# Transmitter.net
KiCad netlist of a schematic drawn in Altium Designer
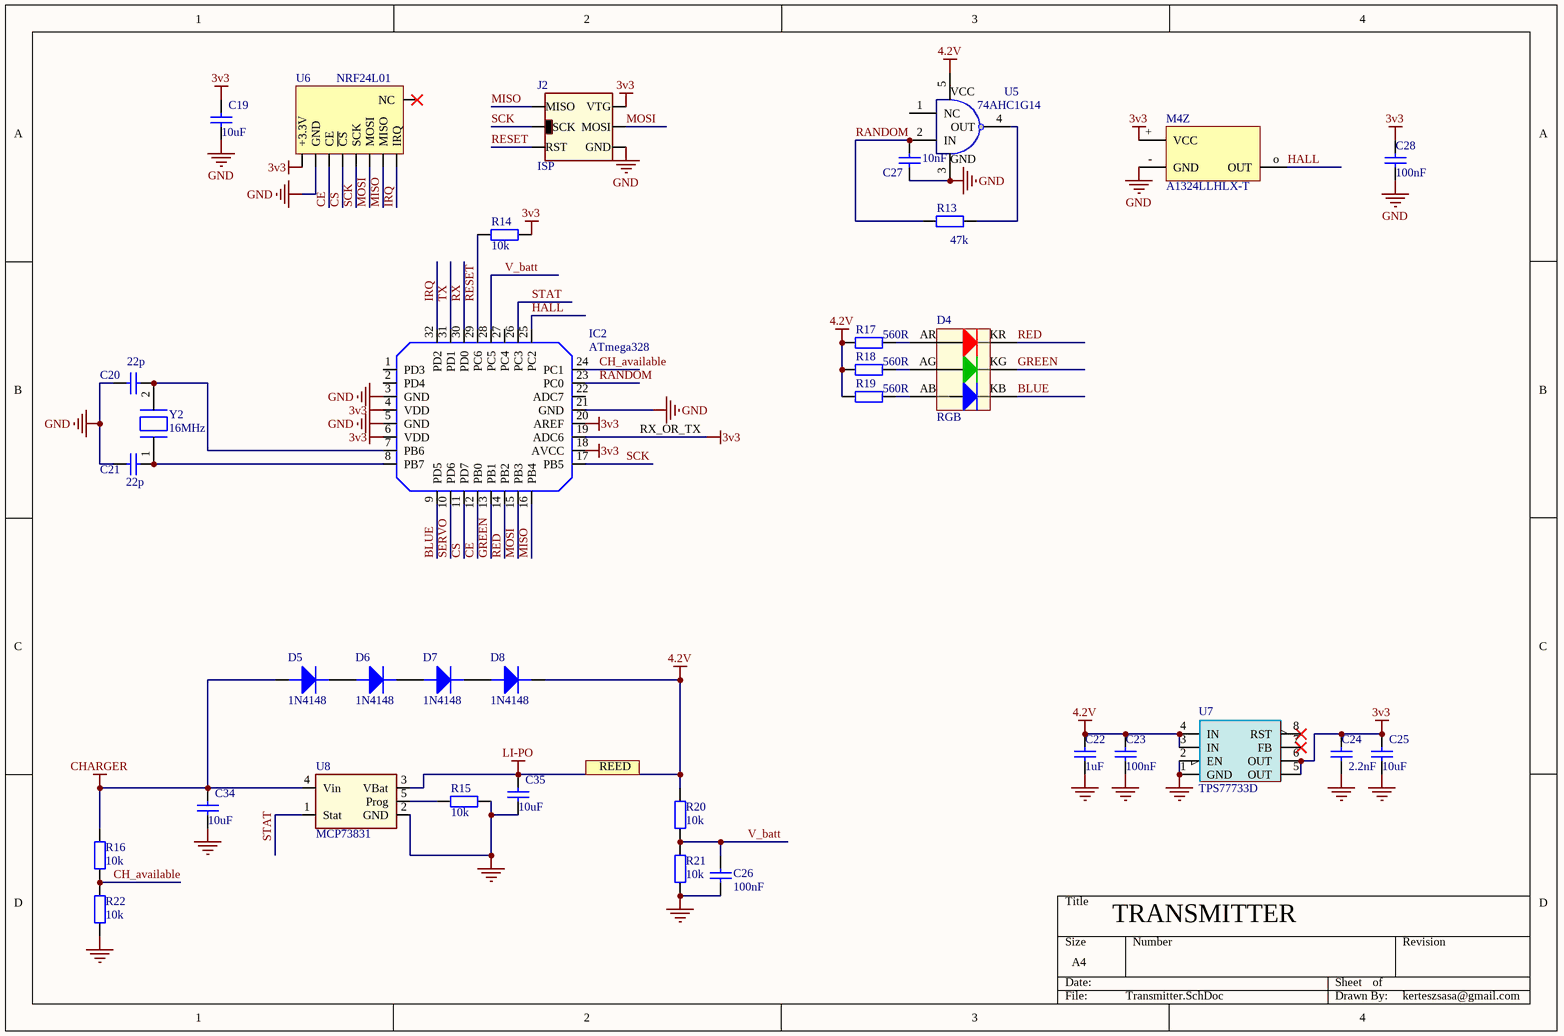
[diagram p0: Transmitter.SchDoc]

(export (version "E")
  (design (tool "Eeschema 10.0.6"))
  (components
    (comp (ref "C19")
      (value "10uF")
      (footprint "FP_0603_CAP_080")
      (description "Capacitor")
      (libsource (lib "Miscellaneous Devices") (part "Cap"))
    )
    (comp (ref "C20")
      (value "22p")
      (footprint "FP_0603_CAP_080")
      (description "Capacitor")
      (libsource (lib "Miscellaneous Devices") (part "Cap"))
    )
    (comp (ref "C21")
      (value "22p")
      (footprint "FP_0603_CAP_080")
      (description "Capacitor")
      (libsource (lib "Miscellaneous Devices") (part "Cap"))
    )
    (comp (ref "C22")
      (value "1uF")
      (footprint "FP_0603_CAP_080")
      (description "Capacitor")
      (libsource (lib "Miscellaneous Devices") (part "Cap"))
    )
    (comp (ref "C23")
      (value "100nF")
      (footprint "FP_0603_CAP_080")
      (description "Capacitor")
      (libsource (lib "Miscellaneous Devices") (part "Cap"))
    )
    (comp (ref "C24")
      (value "2.2nF")
      (footprint "FP_0603_CAP_080")
      (description "Capacitor")
      (libsource (lib "Miscellaneous Devices") (part "Cap"))
    )
    (comp (ref "C25")
      (value "10uF")
      (footprint "FP_0603_CAP_080")
      (description "Capacitor")
      (libsource (lib "Miscellaneous Devices") (part "Cap"))
    )
    (comp (ref "C26")
      (value "100nF")
      (footprint "FP_0603_CAP_080")
      (description "Capacitor")
      (libsource (lib "Miscellaneous Devices") (part "Cap"))
    )
    (comp (ref "C27")
      (value "10nF")
      (footprint "FP_0603_CAP_080")
      (description "Capacitor")
      (libsource (lib "Miscellaneous Devices") (part "Cap"))
    )
    (comp (ref "C28")
      (value "100nF")
      (footprint "FP_0603_CAP_080")
      (description "Capacitor")
      (libsource (lib "Miscellaneous Devices") (part "Cap"))
    )
    (comp (ref "C34")
      (value "10uF")
      (footprint "FP_0603_CAP_080")
      (description "Capacitor")
      (libsource (lib "Miscellaneous Devices") (part "Cap"))
    )
    (comp (ref "C35")
      (value "10uF")
      (footprint "FP_0603_CAP_080")
      (description "Capacitor")
      (libsource (lib "Miscellaneous Devices") (part "Cap"))
    )
    (comp (ref "D4")
      (value "RGB")
      (footprint "RGB_LED_5.0x5.0mm")
      (description "LED_RGB_6_PIN")
      (libsource (lib "Led_optical") (part "LED_RGB_6_PIN"))
    )
    (comp (ref "D5")
      (value "1N4148")
      (footprint "SOD-80")
      (description "Diode 1N4148 SMD")
      (libsource (lib "Diode") (part "DIODE_big"))
    )
    (comp (ref "D6")
      (value "1N4148")
      (footprint "SOD-80")
      (description "Diode 1N4148 SMD")
      (libsource (lib "Diode") (part "DIODE_big"))
    )
    (comp (ref "D7")
      (value "1N4148")
      (footprint "SOD-80")
      (description "Diode 1N4148 SMD")
      (libsource (lib "Diode") (part "DIODE_big"))
    )
    (comp (ref "D8")
      (value "1N4148")
      (footprint "SOD-80")
      (description "Diode 1N4148 SMD")
      (libsource (lib "Diode") (part "DIODE_big"))
    )
    (comp (ref "IC2") (value "ATmega328") (footprint "TQFP32_N") (libsource (lib "uC") (part "ATmega328")))
    (comp (ref "J2")
      (value "ISP")
      (footprint "AVR_ISP")
      (description "Programozó csatlakozó")
      (libsource (lib "Connector") (part "ISP"))
    )
    (comp (ref "M4Z")
      (value "A1324LLHLX-T")
      (footprint "Sensoe_hall_SOT23")
      (description "Hall-Effect Switch for High-Temperature Operation")
      (libsource (lib "Sensor") (part "A3122EUA"))
    )
    (comp (ref "R13")
      (value "47k")
      (footprint "FP_0603_RES")
      (description "Resistor")
      (libsource (lib "") (part "Res3_1"))
    )
    (comp (ref "R14")
      (value "10k")
      (footprint "FP_0603_RES")
      (description "Resistor")
      (libsource (lib "") (part "Res3_2"))
    )
    (comp (ref "R15")
      (value "10k")
      (footprint "FP_0603_RES")
      (description "Resistor")
      (libsource (lib "") (part "Res3_1"))
    )
    (comp (ref "R16")
      (value "10k")
      (footprint "FP_0603_RES")
      (description "Resistor")
      (libsource (lib "Miscellaneous Devices") (part "Res3"))
    )
    (comp (ref "R17")
      (value "560R")
      (footprint "FP_0603_RES")
      (description "Resistor")
      (libsource (lib "") (part "Res3_1"))
    )
    (comp (ref "R18")
      (value "560R")
      (footprint "FP_0603_RES")
      (description "Resistor")
      (libsource (lib "") (part "Res3_1"))
    )
    (comp (ref "R19")
      (value "560R")
      (footprint "FP_0603_RES")
      (description "Resistor")
      (libsource (lib "") (part "Res3_1"))
    )
    (comp (ref "R20")
      (value "10k")
      (footprint "FP_0603_RES")
      (description "Resistor")
      (libsource (lib "Miscellaneous Devices") (part "Res3"))
    )
    (comp (ref "R21")
      (value "10k")
      (footprint "FP_0603_RES")
      (description "Resistor")
      (libsource (lib "Miscellaneous Devices") (part "Res3"))
    )
    (comp (ref "R22")
      (value "10k")
      (footprint "FP_0603_RES")
      (description "Resistor")
      (libsource (lib "Miscellaneous Devices") (part "Res3"))
    )
    (comp (ref "U5")
      (value "74AHC1G14")
      (footprint "GATE_SOT23-5")
      (description "SCHMITT-TRIGGER INVERTER")
      (libsource (lib "Logic_gate") (part "74AHC1G14"))
    )
    (comp (ref "U6")
      (value "NRF24L01")
      (footprint "NRF24L01_SMD")
      (description "2.4Ghz RF module")
      (libsource (lib "Modul") (part "NRF24L01"))
    )
    (comp (ref "U7")
      (value "TPS77733D")
      (footprint "DIGITAL_SOIC8")
      (description "LDO Voltage Regulators Fast-Tran-Res 750-mA")
      (libsource (lib "TPS77733D") (part "TPS77733D"))
    )
    (comp (ref "U8")
      (value "MCP73831")
      (footprint "SUPPLY_SOT23-5")
      (description "MCP73831 SOT23-5 Li-on batt charger")
      (libsource (lib "Supply") (part "MCP73831"))
    )
    (comp (ref "Y2")
      (value "16MHz")
      (footprint "FP_CRYSTAL_HC49_SMD")
      (description "Standard HC49 quartz")
      (libsource (lib "Fufi_altium_lib") (part "XTAL HC49"))
    )
  )
  (nets
    (net (code "1") (name "/BLUE") (class "Default")
      (node (ref "D4") (pin "KB") (pinfunction "R_KB") (pintype "passive"))
      (node (ref "IC2") (pin "9") (pinfunction "PD5_9") (pintype "passive"))
    )
    (net (code "2") (name "/CE") (class "Default")
      (node (ref "IC2") (pin "12") (pinfunction "PB0_12") (pintype "passive"))
      (node (ref "U6") (pin "3") (pinfunction "CE_3") (pintype "passive"))
    )
    (net (code "3") (name "/CH_available") (class "Default")
      (node (ref "IC2") (pin "24") (pinfunction "PC1_24") (pintype "passive"))
      (node (ref "R16") (pin "1") (pinfunction "1_1") (pintype "passive"))
      (node (ref "R22") (pin "2") (pinfunction "2_2") (pintype "passive"))
    )
    (net (code "4") (name "/CS") (class "Default")
      (node (ref "IC2") (pin "11") (pinfunction "PD7_11") (pintype "passive"))
      (node (ref "U6") (pin "4") (pinfunction "~{CS}_4") (pintype "passive"))
    )
    (net (code "5") (name "/GREEN") (class "Default")
      (node (ref "D4") (pin "KG") (pinfunction "G_KG") (pintype "passive"))
      (node (ref "IC2") (pin "13") (pinfunction "PB1_13") (pintype "passive"))
    )
    (net (code "6") (name "/HALL") (class "Default")
      (node (ref "IC2") (pin "25") (pinfunction "PC2_25") (pintype "passive"))
      (node (ref "M4Z") (pin "o") (pinfunction "OUT_o") (pintype "open_collector"))
    )
    (net (code "7") (name "/IRQ") (class "Default")
      (node (ref "IC2") (pin "32") (pinfunction "PD2_32") (pintype "passive"))
      (node (ref "U6") (pin "8") (pinfunction "IRQ_8") (pintype "passive"))
    )
    (net (code "8") (name "/MISO") (class "Default")
      (node (ref "IC2") (pin "16") (pinfunction "PB4_16") (pintype "passive"))
      (node (ref "J2") (pin "1") (pinfunction "MISO_1") (pintype "passive"))
      (node (ref "U6") (pin "7") (pinfunction "MISO_7") (pintype "passive"))
    )
    (net (code "9") (name "/MOSI") (class "Default")
      (node (ref "IC2") (pin "15") (pinfunction "PB3_15") (pintype "passive"))
      (node (ref "J2") (pin "4") (pinfunction "MOSI_4") (pintype "passive"))
      (node (ref "U6") (pin "6") (pinfunction "MOSI_6") (pintype "passive"))
    )
    (net (code "10") (name "/RANDOM") (class "Default")
      (node (ref "C27") (pin "2") (pinfunction "2_2") (pintype "passive"))
      (node (ref "IC2") (pin "23") (pinfunction "PC0_23") (pintype "passive"))
      (node (ref "R13") (pin "2") (pinfunction "2_2") (pintype "passive"))
      (node (ref "U5") (pin "2") (pinfunction "IN_2") (pintype "passive"))
    )
    (net (code "11") (name "/RED") (class "Default")
      (node (ref "D4") (pin "KR") (pinfunction "B_KR") (pintype "passive"))
      (node (ref "IC2") (pin "14") (pinfunction "PB2_14") (pintype "passive"))
    )
    (net (code "12") (name "/RESET") (class "Default")
      (node (ref "IC2") (pin "29") (pinfunction "PC6_29") (pintype "passive"))
      (node (ref "J2") (pin "5") (pinfunction "RST_5") (pintype "passive"))
      (node (ref "R14") (pin "1") (pinfunction "1_1") (pintype "passive"))
    )
    (net (code "13") (name "/RX") (class "Default")
      (node (ref "IC2") (pin "30") (pinfunction "PD0_30") (pintype "passive"))
    )
    (net (code "14") (name "/SCK") (class "Default")
      (node (ref "IC2") (pin "17") (pinfunction "PB5_17") (pintype "passive"))
      (node (ref "J2") (pin "3") (pinfunction "SCK_3") (pintype "passive"))
      (node (ref "U6") (pin "5") (pinfunction "SCK_5") (pintype "passive"))
    )
    (net (code "15") (name "/SERVO") (class "Default")
      (node (ref "IC2") (pin "10") (pinfunction "PD6_10") (pintype "passive"))
    )
    (net (code "16") (name "/STAT") (class "Default")
      (node (ref "IC2") (pin "26") (pinfunction "PC3_26") (pintype "passive"))
      (node (ref "U8") (pin "1") (pinfunction "Stat_1") (pintype "passive"))
    )
    (net (code "17") (name "/TX") (class "Default")
      (node (ref "IC2") (pin "31") (pinfunction "PD1_31") (pintype "passive"))
    )
    (net (code "18") (name "/V_batt") (class "Default")
      (node (ref "C26") (pin "1") (pinfunction "1_1") (pintype "passive"))
      (node (ref "IC2") (pin "28") (pinfunction "PC5_28") (pintype "passive"))
      (node (ref "R20") (pin "1") (pinfunction "1_1") (pintype "passive"))
      (node (ref "R21") (pin "2") (pinfunction "2_2") (pintype "passive"))
    )
    (net (code "19") (name "3v3") (class "Default")
      (node (ref "C19") (pin "2") (pinfunction "2_2") (pintype "passive"))
      (node (ref "C24") (pin "2") (pinfunction "2_2") (pintype "passive"))
      (node (ref "C25") (pin "2") (pinfunction "2_2") (pintype "passive"))
      (node (ref "C28") (pin "2") (pinfunction "2_2") (pintype "passive"))
      (node (ref "IC2") (pin "18") (pinfunction "AVCC_18") (pintype "passive"))
      (node (ref "IC2") (pin "19") (pinfunction "ADC6_19") (pintype "passive"))
      (node (ref "IC2") (pin "20") (pinfunction "AREF_20") (pintype "passive"))
      (node (ref "IC2") (pin "4") (pinfunction "VDD_4") (pintype "passive"))
      (node (ref "IC2") (pin "6") (pinfunction "VDD_6") (pintype "passive"))
      (node (ref "J2") (pin "2") (pinfunction "VTG_2") (pintype "passive"))
      (node (ref "M4Z") (pin "+") (pinfunction "VCC_+") (pintype "power_in"))
      (node (ref "R14") (pin "2") (pinfunction "2_2") (pintype "passive"))
      (node (ref "U6") (pin "1") (pinfunction "+3.3V_1") (pintype "passive"))
      (node (ref "U7") (pin "5") (pinfunction "OUT_5") (pintype "passive"))
      (node (ref "U7") (pin "6") (pinfunction "OUT_6") (pintype "passive"))
    )
    (net (code "20") (name "4.2V") (class "Default")
      (node (ref "C22") (pin "2") (pinfunction "2_2") (pintype "passive"))
      (node (ref "C23") (pin "2") (pinfunction "2_2") (pintype "passive"))
      (node (ref "D8") (pin "K") (pinfunction "K_K") (pintype "passive"))
      (node (ref "R17") (pin "2") (pinfunction "2_2") (pintype "passive"))
      (node (ref "R18") (pin "2") (pinfunction "2_2") (pintype "passive"))
      (node (ref "R19") (pin "2") (pinfunction "2_2") (pintype "passive"))
      (node (ref "R20") (pin "2") (pinfunction "2_2") (pintype "passive"))
      (node (ref "U5") (pin "5") (pinfunction "VCC_5") (pintype "passive"))
      (node (ref "U7") (pin "3") (pinfunction "IN_3") (pintype "passive"))
      (node (ref "U7") (pin "4") (pinfunction "IN_4") (pintype "passive"))
    )
    (net (code "21") (name "CHARGER") (class "Default")
      (node (ref "C34") (pin "2") (pinfunction "2_2") (pintype "passive"))
      (node (ref "D5") (pin "A") (pinfunction "A_A") (pintype "passive"))
      (node (ref "R16") (pin "2") (pinfunction "2_2") (pintype "passive"))
      (node (ref "U8") (pin "4") (pinfunction "Vin_4") (pintype "passive"))
    )
    (net (code "22") (name "GND") (class "Default")
      (node (ref "C19") (pin "1") (pinfunction "1_1") (pintype "passive"))
      (node (ref "C20") (pin "1") (pinfunction "1_1") (pintype "passive"))
      (node (ref "C21") (pin "1") (pinfunction "1_1") (pintype "passive"))
      (node (ref "C22") (pin "1") (pinfunction "1_1") (pintype "passive"))
      (node (ref "C23") (pin "1") (pinfunction "1_1") (pintype "passive"))
      (node (ref "C24") (pin "1") (pinfunction "1_1") (pintype "passive"))
      (node (ref "C25") (pin "1") (pinfunction "1_1") (pintype "passive"))
      (node (ref "C26") (pin "2") (pinfunction "2_2") (pintype "passive"))
      (node (ref "C27") (pin "1") (pinfunction "1_1") (pintype "passive"))
      (node (ref "C28") (pin "1") (pinfunction "1_1") (pintype "passive"))
      (node (ref "C34") (pin "1") (pinfunction "1_1") (pintype "passive"))
      (node (ref "C35") (pin "1") (pinfunction "1_1") (pintype "passive"))
      (node (ref "IC2") (pin "21") (pinfunction "GND_21") (pintype "passive"))
      (node (ref "IC2") (pin "3") (pinfunction "GND_3") (pintype "passive"))
      (node (ref "IC2") (pin "5") (pinfunction "GND_5") (pintype "passive"))
      (node (ref "J2") (pin "6") (pinfunction "GND_6") (pintype "passive"))
      (node (ref "M4Z") (pin "-") (pinfunction "GND_-") (pintype "power_in"))
      (node (ref "R15") (pin "1") (pinfunction "1_1") (pintype "passive"))
      (node (ref "R21") (pin "1") (pinfunction "1_1") (pintype "passive"))
      (node (ref "R22") (pin "1") (pinfunction "1_1") (pintype "passive"))
      (node (ref "U5") (pin "3") (pinfunction "GND_3") (pintype "passive"))
      (node (ref "U6") (pin "2") (pinfunction "GND_2") (pintype "passive"))
      (node (ref "U7") (pin "1") (pinfunction "GND_1") (pintype "passive"))
      (node (ref "U7") (pin "2") (pinfunction "EN_2") (pintype "passive"))
      (node (ref "U8") (pin "2") (pinfunction "GND_2") (pintype "passive"))
    )
    (net (code "23") (name "LI-PO") (class "Default")
      (node (ref "C35") (pin "2") (pinfunction "2_2") (pintype "passive"))
      (node (ref "U8") (pin "3") (pinfunction "VBat_3") (pintype "passive"))
    )
    (net (code "24") (name "Net-(D4-A-PadAB)") (class "Default")
      (node (ref "D4") (pin "AB") (pinfunction "A_AB") (pintype "passive"))
      (node (ref "R19") (pin "1") (pinfunction "1_1") (pintype "passive"))
    )
    (net (code "25") (name "Net-(D4-A-PadAG)") (class "Default")
      (node (ref "D4") (pin "AG") (pinfunction "A_AG") (pintype "passive"))
      (node (ref "R18") (pin "1") (pinfunction "1_1") (pintype "passive"))
    )
    (net (code "26") (name "Net-(D4-A-PadAR)") (class "Default")
      (node (ref "D4") (pin "AR") (pinfunction "A_AR") (pintype "passive"))
      (node (ref "R17") (pin "1") (pinfunction "1_1") (pintype "passive"))
    )
    (net (code "27") (name "Net-(D5-PadK)") (class "Default")
      (node (ref "D5") (pin "K") (pinfunction "K_K") (pintype "passive"))
      (node (ref "D6") (pin "A") (pinfunction "A_A") (pintype "passive"))
    )
    (net (code "28") (name "Net-(D6-PadK)") (class "Default")
      (node (ref "D6") (pin "K") (pinfunction "K_K") (pintype "passive"))
      (node (ref "D7") (pin "A") (pinfunction "A_A") (pintype "passive"))
    )
    (net (code "29") (name "Net-(D7-PadK)") (class "Default")
      (node (ref "D7") (pin "K") (pinfunction "K_K") (pintype "passive"))
      (node (ref "D8") (pin "A") (pinfunction "A_A") (pintype "passive"))
    )
    (net (code "30") (name "Net-(IC2-PB6)") (class "Default")
      (node (ref "C20") (pin "2") (pinfunction "2_2") (pintype "passive"))
      (node (ref "IC2") (pin "7") (pinfunction "PB6_7") (pintype "passive"))
      (node (ref "Y2") (pin "2") (pinfunction "2_2") (pintype "passive"))
    )
    (net (code "31") (name "Net-(IC2-PB7)") (class "Default")
      (node (ref "C21") (pin "2") (pinfunction "2_2") (pintype "passive"))
      (node (ref "IC2") (pin "8") (pinfunction "PB7_8") (pintype "passive"))
      (node (ref "Y2") (pin "1") (pinfunction "1_1") (pintype "passive"))
    )
    (net (code "32") (name "Net-(U5-OUT)") (class "Default")
      (node (ref "R13") (pin "1") (pinfunction "1_1") (pintype "passive"))
      (node (ref "U5") (pin "4") (pinfunction "OUT_4") (pintype "passive"))
    )
    (net (code "33") (name "Net-(U8-Prog)") (class "Default")
      (node (ref "R15") (pin "2") (pinfunction "2_2") (pintype "passive"))
      (node (ref "U8") (pin "5") (pinfunction "Prog_5") (pintype "passive"))
    )
    (net (code "34") (name "unconnected-(IC2-ADC7-Pad22)") (class "Default")
      (node (ref "IC2") (pin "22") (pinfunction "ADC7_22") (pintype "passive"))
    )
    (net (code "35") (name "unconnected-(IC2-PC4-Pad27)") (class "Default")
      (node (ref "IC2") (pin "27") (pinfunction "PC4_27") (pintype "passive"))
    )
    (net (code "36") (name "unconnected-(IC2-PD3-Pad1)") (class "Default")
      (node (ref "IC2") (pin "1") (pinfunction "PD3_1") (pintype "passive"))
    )
    (net (code "37") (name "unconnected-(IC2-PD4-Pad2)") (class "Default")
      (node (ref "IC2") (pin "2") (pinfunction "PD4_2") (pintype "passive"))
    )
    (net (code "38") (name "unconnected-(U5-NC-Pad1)") (class "Default")
      (node (ref "U5") (pin "1") (pinfunction "NC_1") (pintype "passive"))
    )
    (net (code "39") (name "unconnected-(U6-NC-Pad9)") (class "Default")
      (node (ref "U6") (pin "9") (pinfunction "NC_9") (pintype "passive+no_connect"))
    )
    (net (code "40") (name "unconnected-(U7-FB-Pad7)") (class "Default")
      (node (ref "U7") (pin "7") (pinfunction "FB_7") (pintype "passive+no_connect"))
    )
    (net (code "41") (name "unconnected-(U7-RST-Pad8)") (class "Default")
      (node (ref "U7") (pin "8") (pinfunction "RST_8") (pintype "passive+no_connect"))
    )
  )
)
